# ATTINY85-USB.net
KiCad netlist of a schematic drawn in EAGLE
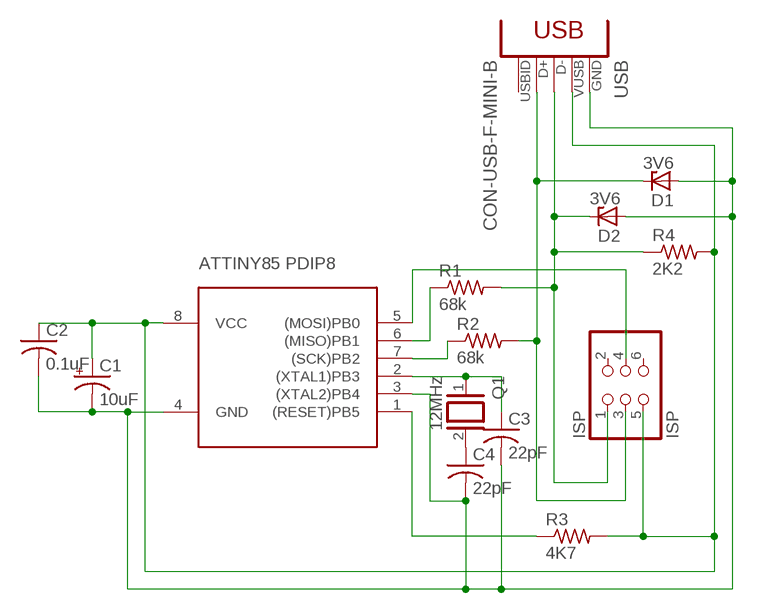
[diagram p0: schematic, sheet 1]

(export (version "E")
  (design (tool "Eeschema 10.0.6"))
  (components
    (comp (ref "C1")
      (value "10uF")
      (footprint "eagle-import:E2-4")
      (libsource (lib "eagle-import") (part "CPOL-USE2-4"))
    )
    (comp (ref "C2")
      (value "0.1uF")
      (footprint "eagle-import:C025-024X044")
      (libsource (lib "eagle-import") (part "C-US025-024X044"))
    )
    (comp (ref "C3")
      (value "22pF")
      (footprint "eagle-import:C025-024X044")
      (libsource (lib "eagle-import") (part "C-US025-024X044"))
    )
    (comp (ref "C4")
      (value "22pF")
      (footprint "eagle-import:C025-024X044")
      (libsource (lib "eagle-import") (part "C-US025-024X044"))
    )
    (comp (ref "D1")
      (value "3V6")
      (footprint "eagle-import:DO34Z7")
      (libsource (lib "eagle-import") (part "ZENER-DIODEDO34-7"))
    )
    (comp (ref "D2")
      (value "3V6")
      (footprint "eagle-import:DO34Z7")
      (libsource (lib "eagle-import") (part "ZENER-DIODEDO34-7"))
    )
    (comp (ref "IC1")
      (value "TINY85")
      (footprint "eagle-import:DIL08")
      (libsource (lib "eagle-import") (part "ATTINY85-PDIP8"))
    )
    (comp (ref "ISP")
      (value "ISP")
      (footprint "eagle-import:2X03")
      (libsource (lib "eagle-import") (part "PINHD-2X3"))
    )
    (comp (ref "Q1")
      (value "12MHz")
      (footprint "eagle-import:QS")
      (libsource (lib "eagle-import") (part "XTAL/S"))
    )
    (comp (ref "R1")
      (value "68k")
      (footprint "eagle-import:0207_9")
      (libsource (lib "eagle-import") (part "R-US_0207/9"))
    )
    (comp (ref "R2")
      (value "68k")
      (footprint "eagle-import:0207_9")
      (libsource (lib "eagle-import") (part "R-US_0207/9"))
    )
    (comp (ref "R3")
      (value "4K7")
      (footprint "eagle-import:0207_9")
      (libsource (lib "eagle-import") (part "R-US_0207/9"))
    )
    (comp (ref "R4")
      (value "2K2")
      (footprint "eagle-import:0207_9")
      (libsource (lib "eagle-import") (part "R-US_0207/9"))
    )
    (comp (ref "USB")
      (value "CON-USB-F-MINI-B")
      (footprint "eagle-import:CONN_USB_MINI-B")
      (libsource (lib "eagle-import") (part "CON-USB-F-MINI-B"))
    )
  )
  (nets
    (net (code "1") (name "Net-(C4-Pad1)") (class "Default")
      (node (ref "C4") (pin "1") (pinfunction "1_1") (pintype "passive"))
      (node (ref "Q1") (pin "2") (pinfunction "2_2") (pintype "passive"))
    )
    (net (code "2") (name "Net-(D1-PadC)") (class "Default")
      (node (ref "D1") (pin "C") (pinfunction "C_C") (pintype "passive"))
      (node (ref "ISP") (pin "3") (pinfunction "3_3") (pintype "passive"))
      (node (ref "R2") (pin "2") (pinfunction "2_2") (pintype "passive"))
      (node (ref "USB") (pin "D+") (pinfunction "D+_D+") (pintype "bidirectional"))
    )
    (net (code "3") (name "Net-(D2-PadC)") (class "Default")
      (node (ref "D2") (pin "C") (pinfunction "C_C") (pintype "passive"))
      (node (ref "ISP") (pin "1") (pinfunction "1_1") (pintype "passive"))
      (node (ref "R1") (pin "2") (pinfunction "2_2") (pintype "passive"))
      (node (ref "R4") (pin "1") (pinfunction "1_1") (pintype "passive"))
      (node (ref "USB") (pin "D-") (pinfunction "D-_D-") (pintype "bidirectional"))
    )
    (net (code "4") (name "Net-(IC1-(MISO)PB1)") (class "Default")
      (node (ref "IC1") (pin "6") (pinfunction "(MISO)PB1_6") (pintype "bidirectional"))
      (node (ref "R1") (pin "1") (pinfunction "1_1") (pintype "passive"))
    )
    (net (code "5") (name "Net-(IC1-(MOSI)PB0)") (class "Default")
      (node (ref "IC1") (pin "5") (pinfunction "(MOSI)PB0_5") (pintype "bidirectional"))
      (node (ref "ISP") (pin "4") (pinfunction "4_4") (pintype "passive"))
    )
    (net (code "6") (name "Net-(IC1-(RESET)PB5)") (class "Default")
      (node (ref "IC1") (pin "1") (pinfunction "(RESET)PB5_1") (pintype "bidirectional"))
      (node (ref "R3") (pin "1") (pinfunction "1_1") (pintype "passive"))
    )
    (net (code "7") (name "Net-(IC1-(SCK)PB2)") (class "Default")
      (node (ref "IC1") (pin "7") (pinfunction "(SCK)PB2_7") (pintype "bidirectional"))
      (node (ref "R2") (pin "1") (pinfunction "1_1") (pintype "passive"))
    )
    (net (code "8") (name "Net-(IC1-(XTAL1)PB3)") (class "Default")
      (node (ref "C3") (pin "1") (pinfunction "1_1") (pintype "passive"))
      (node (ref "IC1") (pin "2") (pinfunction "(XTAL1)PB3_2") (pintype "bidirectional"))
      (node (ref "Q1") (pin "1") (pinfunction "1_1") (pintype "passive"))
    )
    (net (code "9") (name "Net-(IC1-(XTAL2)PB4)") (class "Default")
      (node (ref "C1") (pin "-") (pinfunction "-_-") (pintype "passive"))
      (node (ref "C2") (pin "2") (pinfunction "2_2") (pintype "passive"))
      (node (ref "C3") (pin "2") (pinfunction "2_2") (pintype "passive"))
      (node (ref "C4") (pin "2") (pinfunction "2_2") (pintype "passive"))
      (node (ref "D1") (pin "A") (pinfunction "A_A") (pintype "passive"))
      (node (ref "D2") (pin "A") (pinfunction "A_A") (pintype "passive"))
      (node (ref "IC1") (pin "3") (pinfunction "(XTAL2)PB4_3") (pintype "bidirectional"))
      (node (ref "IC1") (pin "4") (pinfunction "GND_4") (pintype "bidirectional"))
      (node (ref "USB") (pin "GND") (pinfunction "GND_GND") (pintype "bidirectional"))
    )
    (net (code "10") (name "Net-(IC1-VCC)") (class "Default")
      (node (ref "C1") (pin "+") (pinfunction "+_+") (pintype "passive"))
      (node (ref "C2") (pin "1") (pinfunction "1_1") (pintype "passive"))
      (node (ref "IC1") (pin "8") (pinfunction "VCC_8") (pintype "bidirectional"))
      (node (ref "ISP") (pin "5") (pinfunction "5_5") (pintype "passive"))
      (node (ref "R3") (pin "2") (pinfunction "2_2") (pintype "passive"))
      (node (ref "R4") (pin "2") (pinfunction "2_2") (pintype "passive"))
      (node (ref "USB") (pin "VUSB") (pinfunction "VUSB_VUSB") (pintype "bidirectional"))
    )
    (net (code "11") (name "unconnected-(ISP-Pad2)") (class "Default")
      (node (ref "ISP") (pin "2") (pinfunction "2_2") (pintype "passive"))
    )
    (net (code "12") (name "unconnected-(ISP-Pad6)") (class "Default")
      (node (ref "ISP") (pin "6") (pinfunction "6_6") (pintype "passive"))
    )
    (net (code "13") (name "unconnected-(USBB-USBID-PadID)") (class "Default")
      (node (ref "USB") (pin "ID") (pinfunction "USBID_ID") (pintype "bidirectional"))
    )
  )
)
